# geigerzaehler_board.net
KiCad netlist of a schematic drawn in EAGLE
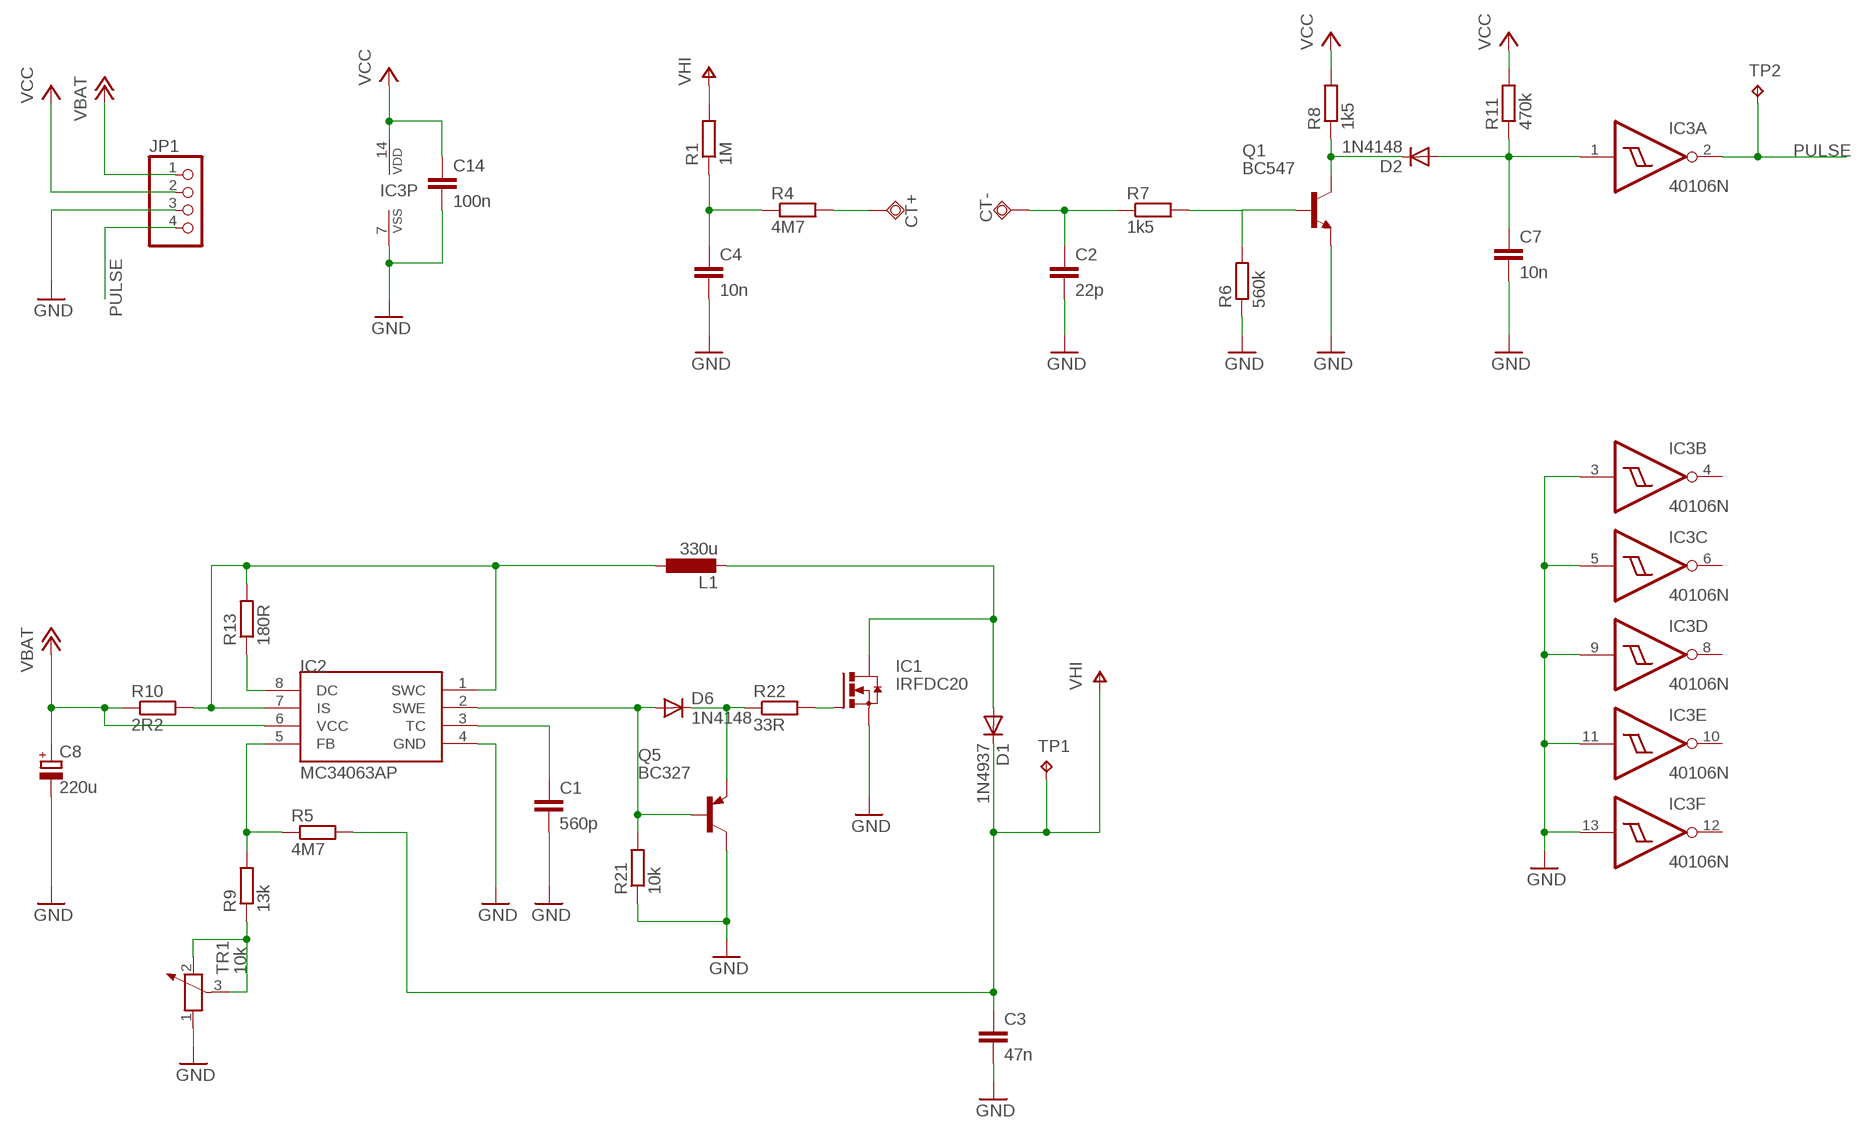
[diagram p0: schematic, sheet 1]

(export (version "E")
  (design (tool "Eeschema 10.0.6"))
  (components
    (comp (ref "C1")
      (value "560p")
      (footprint "eagle-import:C025-025X050")
      (libsource (lib "eagle-import") (part "C-EU025-025X050"))
    )
    (comp (ref "C2")
      (value "22p")
      (footprint "eagle-import:C025-025X050")
      (libsource (lib "eagle-import") (part "C-EU025-025X050"))
    )
    (comp (ref "C3")
      (value "47n")
      (footprint "eagle-import:C075-052X106")
      (libsource (lib "eagle-import") (part "C-EU075-052X106"))
    )
    (comp (ref "C4")
      (value "10n")
      (footprint "eagle-import:C075-032X103")
      (libsource (lib "eagle-import") (part "C-EU075-032X103"))
    )
    (comp (ref "C7")
      (value "10n")
      (footprint "eagle-import:C050-025X075")
      (libsource (lib "eagle-import") (part "C-EU050-025X075"))
    )
    (comp (ref "C8")
      (value "220u")
      (footprint "eagle-import:E3,5-8")
      (libsource (lib "eagle-import") (part "CPOL-EUE3.5-8"))
    )
    (comp (ref "C14")
      (value "100n")
      (footprint "eagle-import:C050-025X075")
      (libsource (lib "eagle-import") (part "C-EU050-025X075"))
    )
    (comp (ref "CT+")
      (value "TPSQPAD1-13Y")
      (footprint "eagle-import:P1-13Y")
      (libsource (lib "eagle-import") (part "TPSQPAD1-13Y"))
    )
    (comp (ref "CT-")
      (value "TPSQPAD1-13Y")
      (footprint "eagle-import:P1-13Y")
      (libsource (lib "eagle-import") (part "TPSQPAD1-13Y"))
    )
    (comp (ref "D1")
      (value "1N4937")
      (footprint "eagle-import:DO41-10")
      (libsource (lib "eagle-import") (part "1N4933"))
    )
    (comp (ref "D2")
      (value "1N4148")
      (footprint "eagle-import:DO35-10")
      (libsource (lib "eagle-import") (part "1N4148DO35-10"))
    )
    (comp (ref "D6")
      (value "1N4148")
      (footprint "eagle-import:DO35-7")
      (libsource (lib "eagle-import") (part "1N4148DO35-7"))
    )
    (comp (ref "IC1")
      (value "IRFDC20")
      (footprint "eagle-import:DIL04")
      (libsource (lib "eagle-import") (part "IRFDC20"))
    )
    (comp (ref "IC2")
      (value "MC34063AP")
      (footprint "eagle-import:DIL08")
      (libsource (lib "eagle-import") (part "MC34063AP"))
    )
    (comp (ref "IC3")
      (value "40106N")
      (footprint "eagle-import:DIL14")
      (libsource (lib "eagle-import") (part "40106N"))
    )
    (comp (ref "JP1")
      (value "PINHD-1X4")
      (footprint "eagle-import:1X04")
      (libsource (lib "eagle-import") (part "PINHD-1X4"))
    )
    (comp (ref "L1")
      (value "330u")
      (footprint "eagle-import:L-EU5-8")
      (libsource (lib "eagle-import") (part "L-EU5-8"))
    )
    (comp (ref "Q1")
      (value "BC547")
      (footprint "eagle-import:TO92")
      (libsource (lib "eagle-import") (part "BC547"))
    )
    (comp (ref "Q5")
      (value "BC327")
      (footprint "eagle-import:TO92")
      (libsource (lib "eagle-import") (part "BC327"))
    )
    (comp (ref "R1")
      (value "1M")
      (footprint "eagle-import:0207_10")
      (libsource (lib "eagle-import") (part "R-EU_0207/10"))
    )
    (comp (ref "R4")
      (value "4M7")
      (footprint "eagle-import:0207_10")
      (libsource (lib "eagle-import") (part "R-EU_0207/10"))
    )
    (comp (ref "R5")
      (value "4M7")
      (footprint "eagle-import:0207_10")
      (libsource (lib "eagle-import") (part "R-EU_0207/10"))
    )
    (comp (ref "R6")
      (value "560k")
      (footprint "eagle-import:0207_10")
      (libsource (lib "eagle-import") (part "R-EU_0207/10"))
    )
    (comp (ref "R7")
      (value "1k5")
      (footprint "eagle-import:0207_10")
      (libsource (lib "eagle-import") (part "R-EU_0207/10"))
    )
    (comp (ref "R8")
      (value "1k5")
      (footprint "eagle-import:0207_10")
      (libsource (lib "eagle-import") (part "R-EU_0207/10"))
    )
    (comp (ref "R9")
      (value "13k")
      (footprint "eagle-import:0207_10")
      (libsource (lib "eagle-import") (part "R-EU_0207/10"))
    )
    (comp (ref "R10")
      (value "2R2")
      (footprint "eagle-import:0309_12")
      (libsource (lib "eagle-import") (part "R-EU_0309/12"))
    )
    (comp (ref "R11")
      (value "470k")
      (footprint "eagle-import:0207_10")
      (libsource (lib "eagle-import") (part "R-EU_0207/10"))
    )
    (comp (ref "R13")
      (value "180R")
      (footprint "eagle-import:0207_10")
      (libsource (lib "eagle-import") (part "R-EU_0207/10"))
    )
    (comp (ref "R21")
      (value "10k")
      (footprint "eagle-import:0207_10")
      (libsource (lib "eagle-import") (part "R-EU_0207/10"))
    )
    (comp (ref "R22")
      (value "33R")
      (footprint "eagle-import:0207_10")
      (libsource (lib "eagle-import") (part "R-EU_0207/10"))
    )
    (comp (ref "TP1")
      (value "TPPAD1-13Y")
      (footprint "eagle-import:P1-13Y")
      (libsource (lib "eagle-import") (part "TPPAD1-13Y"))
    )
    (comp (ref "TP2")
      (value "TPPAD1-13Y")
      (footprint "eagle-import:P1-13Y")
      (libsource (lib "eagle-import") (part "TPPAD1-13Y"))
    )
    (comp (ref "TR1")
      (value "10k")
      (footprint "eagle-import:PT-SPIN")
      (libsource (lib "eagle-import") (part "POTENTIOMETER_PT_SPIN"))
    )
  )
  (nets
    (net (code "1") (name "/PULSE") (class "Default")
      (node (ref "IC3") (pin "2") (pinfunction "O_2") (pintype "output"))
      (node (ref "JP1") (pin "4") (pinfunction "4_4") (pintype "passive"))
      (node (ref "TP2") (pin "TP") (pinfunction "TP_TP") (pintype "input"))
    )
    (net (code "2") (name "GND") (class "Default")
      (node (ref "C1") (pin "2") (pinfunction "2_2") (pintype "passive"))
      (node (ref "C14") (pin "2") (pinfunction "2_2") (pintype "passive"))
      (node (ref "C2") (pin "2") (pinfunction "2_2") (pintype "passive"))
      (node (ref "C3") (pin "2") (pinfunction "2_2") (pintype "passive"))
      (node (ref "C4") (pin "2") (pinfunction "2_2") (pintype "passive"))
      (node (ref "C7") (pin "2") (pinfunction "2_2") (pintype "passive"))
      (node (ref "C8") (pin "-") (pinfunction "-_-") (pintype "passive"))
      (node (ref "IC1") (pin "4") (pinfunction "S_4") (pintype "passive"))
      (node (ref "IC2") (pin "4") (pinfunction "GND_4") (pintype "passive"))
      (node (ref "IC3") (pin "11") (pinfunction "I_11") (pintype "input"))
      (node (ref "IC3") (pin "13") (pinfunction "I_13") (pintype "input"))
      (node (ref "IC3") (pin "3") (pinfunction "I_3") (pintype "input"))
      (node (ref "IC3") (pin "5") (pinfunction "I_5") (pintype "input"))
      (node (ref "IC3") (pin "7") (pinfunction "VSS_7") (pintype "power_in"))
      (node (ref "IC3") (pin "9") (pinfunction "I_9") (pintype "input"))
      (node (ref "JP1") (pin "3") (pinfunction "3_3") (pintype "passive"))
      (node (ref "Q1") (pin "1") (pinfunction "E_1") (pintype "passive"))
      (node (ref "Q5") (pin "3") (pinfunction "C_3") (pintype "passive"))
      (node (ref "R21") (pin "1") (pinfunction "1_1") (pintype "passive"))
      (node (ref "R6") (pin "1") (pinfunction "1_1") (pintype "passive"))
      (node (ref "TR1") (pin "1") (pinfunction "1_1") (pintype "passive"))
    )
    (net (code "3") (name "Net-(C2-Pad1)") (class "Default")
      (node (ref "C2") (pin "1") (pinfunction "1_1") (pintype "passive"))
      (node (ref "CT-") (pin "TP") (pinfunction "TP_TP") (pintype "input"))
      (node (ref "R7") (pin "1") (pinfunction "1_1") (pintype "passive"))
    )
    (net (code "4") (name "Net-(C4-Pad1)") (class "Default")
      (node (ref "C4") (pin "1") (pinfunction "1_1") (pintype "passive"))
      (node (ref "R1") (pin "1") (pinfunction "1_1") (pintype "passive"))
      (node (ref "R4") (pin "1") (pinfunction "1_1") (pintype "passive"))
    )
    (net (code "5") (name "Net-(CT+-PadTP)") (class "Default")
      (node (ref "CT+") (pin "TP") (pinfunction "TP_TP") (pintype "input"))
      (node (ref "R4") (pin "2") (pinfunction "2_2") (pintype "passive"))
    )
    (net (code "6") (name "Net-(IC1-D)") (class "Default")
      (node (ref "D1") (pin "A") (pinfunction "A_A") (pintype "passive"))
      (node (ref "IC1") (pin "1") (pinfunction "D_1") (pintype "passive"))
      (node (ref "L1") (pin "P$3") (pinfunction "2_P$3") (pintype "passive"))
    )
    (net (code "7") (name "Net-(IC1-G)") (class "Default")
      (node (ref "IC1") (pin "3") (pinfunction "G_3") (pintype "passive"))
      (node (ref "R22") (pin "2") (pinfunction "2_2") (pintype "passive"))
    )
    (net (code "8") (name "Net-(IC2-DC)") (class "Default")
      (node (ref "IC2") (pin "8") (pinfunction "DC_8") (pintype "passive"))
      (node (ref "R13") (pin "1") (pinfunction "1_1") (pintype "passive"))
    )
    (net (code "9") (name "Net-(IC2-FB)") (class "Default")
      (node (ref "IC2") (pin "5") (pinfunction "FB_5") (pintype "passive"))
      (node (ref "R5") (pin "1") (pinfunction "1_1") (pintype "passive"))
      (node (ref "R9") (pin "2") (pinfunction "2_2") (pintype "passive"))
    )
    (net (code "10") (name "Net-(IC2-IS)") (class "Default")
      (node (ref "IC2") (pin "1") (pinfunction "SWC_1") (pintype "passive"))
      (node (ref "IC2") (pin "7") (pinfunction "IS_7") (pintype "passive"))
      (node (ref "L1") (pin "P$1") (pinfunction "1_P$1") (pintype "passive"))
      (node (ref "R10") (pin "2") (pinfunction "2_2") (pintype "passive"))
      (node (ref "R13") (pin "2") (pinfunction "2_2") (pintype "passive"))
    )
    (net (code "11") (name "Net-(IC2-SWE)") (class "Default")
      (node (ref "D6") (pin "A") (pinfunction "A_A") (pintype "passive"))
      (node (ref "IC2") (pin "2") (pinfunction "SWE_2") (pintype "passive"))
      (node (ref "Q5") (pin "2") (pinfunction "B_2") (pintype "passive"))
      (node (ref "R21") (pin "2") (pinfunction "2_2") (pintype "passive"))
    )
    (net (code "12") (name "Net-(IC2-TC)") (class "Default")
      (node (ref "C1") (pin "1") (pinfunction "1_1") (pintype "passive"))
      (node (ref "IC2") (pin "3") (pinfunction "TC_3") (pintype "passive"))
    )
    (net (code "13") (name "Net-(IC3A-I)") (class "Default")
      (node (ref "C7") (pin "1") (pinfunction "1_1") (pintype "passive"))
      (node (ref "D2") (pin "A") (pinfunction "A_A") (pintype "passive"))
      (node (ref "IC3") (pin "1") (pinfunction "I_1") (pintype "input"))
      (node (ref "R11") (pin "1") (pinfunction "1_1") (pintype "passive"))
    )
    (net (code "14") (name "Net-(Q1-B)") (class "Default")
      (node (ref "Q1") (pin "2") (pinfunction "B_2") (pintype "passive"))
      (node (ref "R6") (pin "2") (pinfunction "2_2") (pintype "passive"))
      (node (ref "R7") (pin "2") (pinfunction "2_2") (pintype "passive"))
    )
    (net (code "15") (name "Net-(Q1-C)") (class "Default")
      (node (ref "D2") (pin "C") (pinfunction "C_C") (pintype "passive"))
      (node (ref "Q1") (pin "3") (pinfunction "C_3") (pintype "passive"))
      (node (ref "R8") (pin "1") (pinfunction "1_1") (pintype "passive"))
    )
    (net (code "16") (name "Net-(Q5-E)") (class "Default")
      (node (ref "D6") (pin "C") (pinfunction "C_C") (pintype "passive"))
      (node (ref "Q5") (pin "1") (pinfunction "E_1") (pintype "passive"))
      (node (ref "R22") (pin "1") (pinfunction "1_1") (pintype "passive"))
    )
    (net (code "17") (name "Net-(R9-Pad1)") (class "Default")
      (node (ref "R9") (pin "1") (pinfunction "1_1") (pintype "passive"))
      (node (ref "TR1") (pin "2") (pinfunction "2_2") (pintype "passive"))
      (node (ref "TR1") (pin "3") (pinfunction "3_3") (pintype "passive"))
    )
    (net (code "18") (name "VBAT") (class "Default")
      (node (ref "C8") (pin "+") (pinfunction "+_+") (pintype "passive"))
      (node (ref "IC2") (pin "6") (pinfunction "VCC_6") (pintype "passive"))
      (node (ref "JP1") (pin "1") (pinfunction "1_1") (pintype "passive"))
      (node (ref "R10") (pin "1") (pinfunction "1_1") (pintype "passive"))
    )
    (net (code "19") (name "VCC") (class "Default")
      (node (ref "C14") (pin "1") (pinfunction "1_1") (pintype "passive"))
      (node (ref "IC3") (pin "14") (pinfunction "VDD_14") (pintype "power_in"))
      (node (ref "JP1") (pin "2") (pinfunction "2_2") (pintype "passive"))
      (node (ref "R11") (pin "2") (pinfunction "2_2") (pintype "passive"))
      (node (ref "R8") (pin "2") (pinfunction "2_2") (pintype "passive"))
    )
    (net (code "20") (name "VHI") (class "Default")
      (node (ref "C3") (pin "1") (pinfunction "1_1") (pintype "passive"))
      (node (ref "D1") (pin "C") (pinfunction "C_C") (pintype "passive"))
      (node (ref "R1") (pin "2") (pinfunction "2_2") (pintype "passive"))
      (node (ref "R5") (pin "2") (pinfunction "2_2") (pintype "passive"))
      (node (ref "TP1") (pin "TP") (pinfunction "TP_TP") (pintype "input"))
    )
    (net (code "21") (name "unconnected-(IC3B-O-Pad4)") (class "Default")
      (node (ref "IC3") (pin "4") (pinfunction "O_4") (pintype "output"))
    )
    (net (code "22") (name "unconnected-(IC3C-O-Pad6)") (class "Default")
      (node (ref "IC3") (pin "6") (pinfunction "O_6") (pintype "output"))
    )
    (net (code "23") (name "unconnected-(IC3D-O-Pad8)") (class "Default")
      (node (ref "IC3") (pin "8") (pinfunction "O_8") (pintype "output"))
    )
    (net (code "24") (name "unconnected-(IC3E-O-Pad10)") (class "Default")
      (node (ref "IC3") (pin "10") (pinfunction "O_10") (pintype "output"))
    )
    (net (code "25") (name "unconnected-(IC3F-O-Pad12)") (class "Default")
      (node (ref "IC3") (pin "12") (pinfunction "O_12") (pintype "output"))
    )
  )
)
